# OctoSlime_Haptics_Module.net
KiCad netlist of a schematic drawn in EasyEDA Pro
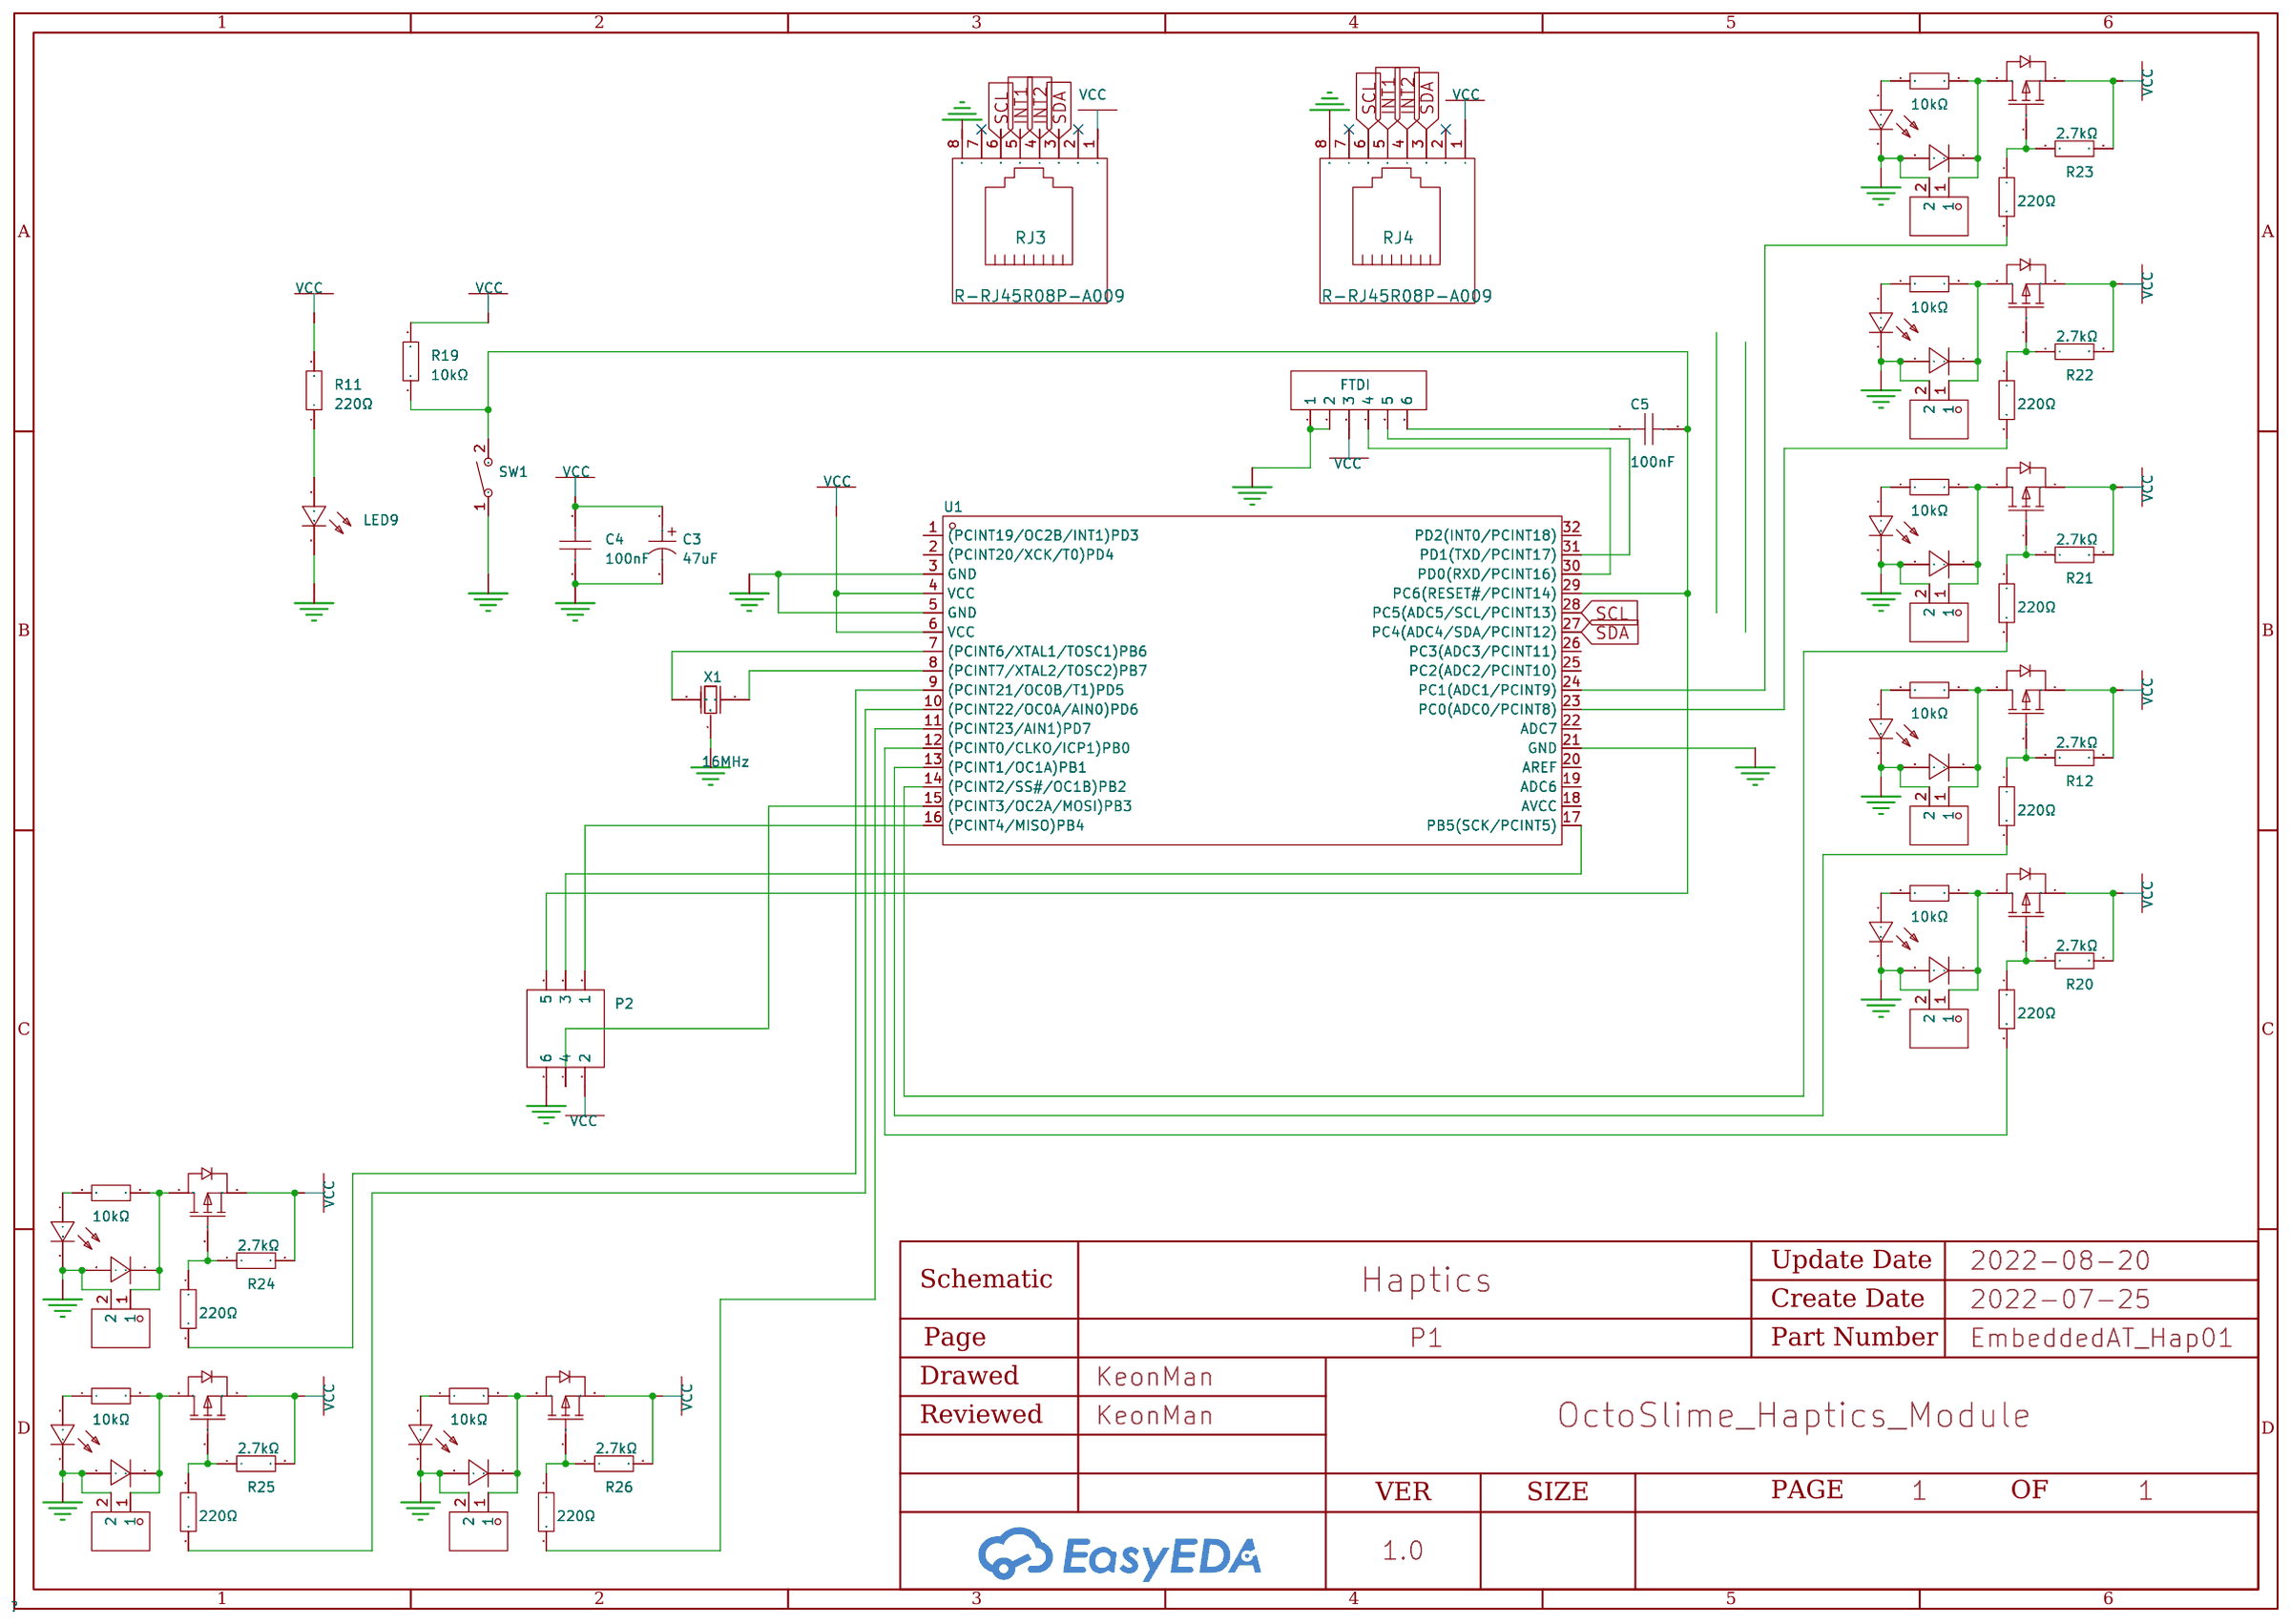
[diagram p0: schematic sheet]

(export (version "E")
  (design (tool "Eeschema 10.0.6"))
  (components
    (comp (ref "C3")
      (value "47uF")
      (footprint "easyedapro:CAP-SMD_L7.3-W4.3-FD")
      (description "容值:47uF;精度:±10%;额定电压:25V;等效串联电阻:900mΩ@100kHz;工作温度:-55~+125;")
      (fields (field (name "Manufacturer Part") "CA45-D-25V-47F-K") (field (name "Manufacturer") "TORCH(火炬)"))
      (libsource (lib "easyedapro") (part "CA45-D-25V-47μF-K"))
    )
    (comp (ref "C4")
      (value "100nF")
      (footprint "easyedapro:C0603")
      (description "容值:100nF;精度:±10%;额定电压:50V;温度系数:X7R;")
      (fields
        (field (name "Manufacturer Part") "CL10B104KB8NNNC")
        (field (name "Manufacturer") "SAMSUNG(三星)")
      )
      (libsource (lib "easyedapro") (part "CL10B104KB8NNNC"))
    )
    (comp (ref "C5")
      (value "100nF")
      (footprint "easyedapro:C0603")
      (description "容值:100nF;精度:±10%;额定电压:50V;温度系数:X7R;")
      (fields
        (field (name "Manufacturer Part") "CL10B104KB8NNNC")
        (field (name "Manufacturer") "SAMSUNG(三星)")
      )
      (libsource (lib "easyedapro") (part "CL10B104KB8NNNC"))
    )
    (comp (ref "CN1")
      (value "~")
      (footprint "easyedapro:CONN-TH_2P-P2.50_HX25003-2WAP")
      (description "俗称： XH2.54 配套：HX25002-2Y")
      (fields (field (name "Manufacturer Part") "HX25003-2WAP") (field (name "Manufacturer") "HX(红星)"))
      (libsource (lib "easyedapro") (part "HX25003-2WAP"))
    )
    (comp (ref "CN2")
      (value "~")
      (footprint "easyedapro:CONN-TH_2P-P2.50_HX25003-2WAP")
      (description "俗称： XH2.54 配套：HX25002-2Y")
      (fields (field (name "Manufacturer Part") "HX25003-2WAP") (field (name "Manufacturer") "HX(红星)"))
      (libsource (lib "easyedapro") (part "HX25003-2WAP"))
    )
    (comp (ref "CN3")
      (value "~")
      (footprint "easyedapro:CONN-TH_2P-P2.50_HX25003-2WAP")
      (description "俗称： XH2.54 配套：HX25002-2Y")
      (fields (field (name "Manufacturer Part") "HX25003-2WAP") (field (name "Manufacturer") "HX(红星)"))
      (libsource (lib "easyedapro") (part "HX25003-2WAP"))
    )
    (comp (ref "CN4")
      (value "~")
      (footprint "easyedapro:CONN-TH_2P-P2.50_HX25003-2WAP")
      (description "俗称： XH2.54 配套：HX25002-2Y")
      (fields (field (name "Manufacturer Part") "HX25003-2WAP") (field (name "Manufacturer") "HX(红星)"))
      (libsource (lib "easyedapro") (part "HX25003-2WAP"))
    )
    (comp (ref "CN5")
      (value "~")
      (footprint "easyedapro:CONN-TH_2P-P2.50_HX25003-2WAP")
      (description "俗称： XH2.54 配套：HX25002-2Y")
      (fields (field (name "Manufacturer Part") "HX25003-2WAP") (field (name "Manufacturer") "HX(红星)"))
      (libsource (lib "easyedapro") (part "HX25003-2WAP"))
    )
    (comp (ref "CN6")
      (value "~")
      (footprint "easyedapro:CONN-TH_2P-P2.50_HX25003-2WAP")
      (description "俗称： XH2.54 配套：HX25002-2Y")
      (fields (field (name "Manufacturer Part") "HX25003-2WAP") (field (name "Manufacturer") "HX(红星)"))
      (libsource (lib "easyedapro") (part "HX25003-2WAP"))
    )
    (comp (ref "CN7")
      (value "~")
      (footprint "easyedapro:CONN-TH_2P-P2.50_HX25003-2WAP")
      (description "俗称： XH2.54 配套：HX25002-2Y")
      (fields (field (name "Manufacturer Part") "HX25003-2WAP") (field (name "Manufacturer") "HX(红星)"))
      (libsource (lib "easyedapro") (part "HX25003-2WAP"))
    )
    (comp (ref "CN8")
      (value "~")
      (footprint "easyedapro:CONN-TH_2P-P2.50_HX25003-2WAP")
      (description "俗称： XH2.54 配套：HX25002-2Y")
      (fields (field (name "Manufacturer Part") "HX25003-2WAP") (field (name "Manufacturer") "HX(红星)"))
      (libsource (lib "easyedapro") (part "HX25003-2WAP"))
    )
    (comp (ref "D1")
      (value "~")
      (footprint "easyedapro:DO-214AC_L4.3-W2.7-LS5.3-RD")
      (description "二极管配置:-;直流反向耐压(Vr):1kV;平均整流电流(Io):1A;正向压降(Vf):1.1V@1A;反向电流(Ir):5A@1kV;")
      (fields (field (name "Manufacturer Part") "M7") (field (name "Manufacturer") "MDD"))
      (libsource (lib "easyedapro") (part "M7_C95872"))
    )
    (comp (ref "D2")
      (value "~")
      (footprint "easyedapro:DO-214AC_L4.3-W2.7-LS5.3-RD")
      (description "二极管配置:-;直流反向耐压(Vr):1kV;平均整流电流(Io):1A;正向压降(Vf):1.1V@1A;反向电流(Ir):5A@1kV;")
      (fields (field (name "Manufacturer Part") "M7") (field (name "Manufacturer") "MDD"))
      (libsource (lib "easyedapro") (part "M7_C95872"))
    )
    (comp (ref "D3")
      (value "~")
      (footprint "easyedapro:DO-214AC_L4.3-W2.7-LS5.3-RD")
      (description "二极管配置:-;直流反向耐压(Vr):1kV;平均整流电流(Io):1A;正向压降(Vf):1.1V@1A;反向电流(Ir):5A@1kV;")
      (fields (field (name "Manufacturer Part") "M7") (field (name "Manufacturer") "MDD"))
      (libsource (lib "easyedapro") (part "M7_C95872"))
    )
    (comp (ref "D4")
      (value "~")
      (footprint "easyedapro:DO-214AC_L4.3-W2.7-LS5.3-RD")
      (description "二极管配置:-;直流反向耐压(Vr):1kV;平均整流电流(Io):1A;正向压降(Vf):1.1V@1A;反向电流(Ir):5A@1kV;")
      (fields (field (name "Manufacturer Part") "M7") (field (name "Manufacturer") "MDD"))
      (libsource (lib "easyedapro") (part "M7_C95872"))
    )
    (comp (ref "D5")
      (value "~")
      (footprint "easyedapro:DO-214AC_L4.3-W2.7-LS5.3-RD")
      (description "二极管配置:-;直流反向耐压(Vr):1kV;平均整流电流(Io):1A;正向压降(Vf):1.1V@1A;反向电流(Ir):5A@1kV;")
      (fields (field (name "Manufacturer Part") "M7") (field (name "Manufacturer") "MDD"))
      (libsource (lib "easyedapro") (part "M7_C95872"))
    )
    (comp (ref "D6")
      (value "~")
      (footprint "easyedapro:DO-214AC_L4.3-W2.7-LS5.3-RD")
      (description "二极管配置:-;直流反向耐压(Vr):1kV;平均整流电流(Io):1A;正向压降(Vf):1.1V@1A;反向电流(Ir):5A@1kV;")
      (fields (field (name "Manufacturer Part") "M7") (field (name "Manufacturer") "MDD"))
      (libsource (lib "easyedapro") (part "M7_C95872"))
    )
    (comp (ref "D7")
      (value "~")
      (footprint "easyedapro:DO-214AC_L4.3-W2.7-LS5.3-RD")
      (description "二极管配置:-;直流反向耐压(Vr):1kV;平均整流电流(Io):1A;正向压降(Vf):1.1V@1A;反向电流(Ir):5A@1kV;")
      (fields (field (name "Manufacturer Part") "M7") (field (name "Manufacturer") "MDD"))
      (libsource (lib "easyedapro") (part "M7_C95872"))
    )
    (comp (ref "D8")
      (value "~")
      (footprint "easyedapro:DO-214AC_L4.3-W2.7-LS5.3-RD")
      (description "二极管配置:-;直流反向耐压(Vr):1kV;平均整流电流(Io):1A;正向压降(Vf):1.1V@1A;反向电流(Ir):5A@1kV;")
      (fields (field (name "Manufacturer Part") "M7") (field (name "Manufacturer") "MDD"))
      (libsource (lib "easyedapro") (part "M7_C95872"))
    )
    (comp (ref "FTDI")
      (value "~")
      (footprint "easyedapro:HDR-TH_6P-P2.54-V-M-1")
      (fields (field (name "Manufacturer Part") "2.54-1x6P直针") (field (name "Manufacturer") "BOOMELE(博穆精密)"))
      (libsource (lib "easyedapro") (part "Header-Male-2.54_1x6"))
    )
    (comp (ref "LED1")
      (value "~")
      (footprint "easyedapro:LED0603-R-RD")
      (description "发光颜色:红灯;")
      (fields
        (field (name "Manufacturer Part") "19-213/R6C-AP1Q2B/3T")
        (field (name "Manufacturer") "EVERLIGHT(台湾亿光)")
      )
      (libsource (lib "easyedapro") (part "19-213/R6C-AP1Q2B/3T_C128051"))
    )
    (comp (ref "LED2")
      (value "~")
      (footprint "easyedapro:LED0603-R-RD")
      (description "发光颜色:红灯;")
      (fields
        (field (name "Manufacturer Part") "19-213/R6C-AP1Q2B/3T")
        (field (name "Manufacturer") "EVERLIGHT(台湾亿光)")
      )
      (libsource (lib "easyedapro") (part "19-213/R6C-AP1Q2B/3T_C128051"))
    )
    (comp (ref "LED3")
      (value "~")
      (footprint "easyedapro:LED0603-R-RD")
      (description "发光颜色:红灯;")
      (fields
        (field (name "Manufacturer Part") "19-213/R6C-AP1Q2B/3T")
        (field (name "Manufacturer") "EVERLIGHT(台湾亿光)")
      )
      (libsource (lib "easyedapro") (part "19-213/R6C-AP1Q2B/3T_C128051"))
    )
    (comp (ref "LED4")
      (value "~")
      (footprint "easyedapro:LED0603-R-RD")
      (description "发光颜色:红灯;")
      (fields
        (field (name "Manufacturer Part") "19-213/R6C-AP1Q2B/3T")
        (field (name "Manufacturer") "EVERLIGHT(台湾亿光)")
      )
      (libsource (lib "easyedapro") (part "19-213/R6C-AP1Q2B/3T_C128051"))
    )
    (comp (ref "LED5")
      (value "~")
      (footprint "easyedapro:LED0603-R-RD")
      (description "发光颜色:红灯;")
      (fields
        (field (name "Manufacturer Part") "19-213/R6C-AP1Q2B/3T")
        (field (name "Manufacturer") "EVERLIGHT(台湾亿光)")
      )
      (libsource (lib "easyedapro") (part "19-213/R6C-AP1Q2B/3T_C128051"))
    )
    (comp (ref "LED6")
      (value "~")
      (footprint "easyedapro:LED0603-R-RD")
      (description "发光颜色:红灯;")
      (fields
        (field (name "Manufacturer Part") "19-213/R6C-AP1Q2B/3T")
        (field (name "Manufacturer") "EVERLIGHT(台湾亿光)")
      )
      (libsource (lib "easyedapro") (part "19-213/R6C-AP1Q2B/3T_C128051"))
    )
    (comp (ref "LED7")
      (value "~")
      (footprint "easyedapro:LED0603-R-RD")
      (description "发光颜色:红灯;")
      (fields
        (field (name "Manufacturer Part") "19-213/R6C-AP1Q2B/3T")
        (field (name "Manufacturer") "EVERLIGHT(台湾亿光)")
      )
      (libsource (lib "easyedapro") (part "19-213/R6C-AP1Q2B/3T_C128051"))
    )
    (comp (ref "LED8")
      (value "~")
      (footprint "easyedapro:LED0603-R-RD")
      (description "发光颜色:红灯;")
      (fields
        (field (name "Manufacturer Part") "19-213/R6C-AP1Q2B/3T")
        (field (name "Manufacturer") "EVERLIGHT(台湾亿光)")
      )
      (libsource (lib "easyedapro") (part "19-213/R6C-AP1Q2B/3T_C128051"))
    )
    (comp (ref "LED9")
      (value "~")
      (footprint "easyedapro:LED0603-R-RD")
      (description "发光颜色:红灯;")
      (fields
        (field (name "Manufacturer Part") "19-213/R6C-AP1Q2B/3T")
        (field (name "Manufacturer") "EVERLIGHT(台湾亿光)")
      )
      (libsource (lib "easyedapro") (part "19-213/R6C-AP1Q2B/3T_C128051"))
    )
    (comp (ref "P2")
      (value "~")
      (footprint "easyedapro:IDC-TH_6P-P2.54_C11214")
      (description "连接器类型:简牛座;间距:2.54mm;排数:2;行距:2.54mm;封装形式:直插;触头材质:黄铜;触头镀层:金;")
      (fields (field (name "Manufacturer Part") "2.54-2*3P简牛") (field (name "Manufacturer") "BOOMELE(博穆精密)"))
      (libsource (lib "easyedapro") (part "HDR-IDC-2.54-2X3P"))
    )
    (comp (ref "Q1")
      (value "~")
      (footprint "easyedapro:SC-70-3_L2.2-W1.2-P1.30-LS2.1-BL")
      (fields (field (name "Manufacturer Part") "CJ2101") (field (name "Manufacturer") "CJ（江苏长电/长晶）"))
      (libsource (lib "easyedapro") (part "CJ2101"))
    )
    (comp (ref "Q2")
      (value "~")
      (footprint "easyedapro:SC-70-3_L2.2-W1.2-P1.30-LS2.1-BL")
      (fields (field (name "Manufacturer Part") "CJ2101") (field (name "Manufacturer") "CJ（江苏长电/长晶）"))
      (libsource (lib "easyedapro") (part "CJ2101"))
    )
    (comp (ref "Q3")
      (value "~")
      (footprint "easyedapro:SC-70-3_L2.2-W1.2-P1.30-LS2.1-BL")
      (fields (field (name "Manufacturer Part") "CJ2101") (field (name "Manufacturer") "CJ（江苏长电/长晶）"))
      (libsource (lib "easyedapro") (part "CJ2101"))
    )
    (comp (ref "Q4")
      (value "~")
      (footprint "easyedapro:SC-70-3_L2.2-W1.2-P1.30-LS2.1-BL")
      (fields (field (name "Manufacturer Part") "CJ2101") (field (name "Manufacturer") "CJ（江苏长电/长晶）"))
      (libsource (lib "easyedapro") (part "CJ2101"))
    )
    (comp (ref "Q5")
      (value "~")
      (footprint "easyedapro:SC-70-3_L2.2-W1.2-P1.30-LS2.1-BL")
      (fields (field (name "Manufacturer Part") "CJ2101") (field (name "Manufacturer") "CJ（江苏长电/长晶）"))
      (libsource (lib "easyedapro") (part "CJ2101"))
    )
    (comp (ref "Q6")
      (value "~")
      (footprint "easyedapro:SC-70-3_L2.2-W1.2-P1.30-LS2.1-BL")
      (fields (field (name "Manufacturer Part") "CJ2101") (field (name "Manufacturer") "CJ（江苏长电/长晶）"))
      (libsource (lib "easyedapro") (part "CJ2101"))
    )
    (comp (ref "Q7")
      (value "~")
      (footprint "easyedapro:SC-70-3_L2.2-W1.2-P1.30-LS2.1-BL")
      (fields (field (name "Manufacturer Part") "CJ2101") (field (name "Manufacturer") "CJ（江苏长电/长晶）"))
      (libsource (lib "easyedapro") (part "CJ2101"))
    )
    (comp (ref "Q8")
      (value "~")
      (footprint "easyedapro:SC-70-3_L2.2-W1.2-P1.30-LS2.1-BL")
      (fields (field (name "Manufacturer Part") "CJ2101") (field (name "Manufacturer") "CJ（江苏长电/长晶）"))
      (libsource (lib "easyedapro") (part "CJ2101"))
    )
    (comp (ref "R1")
      (value "220Ω")
      (footprint "easyedapro:R1206")
      (description "电阻类型:厚膜电阻;阻值:220Ω;精度:±1%;功率:250mW;温度系数:±100ppm/;最大工作电压:200V;工作温度范围:-55~+155;")
      (fields (field (name "Manufacturer Part") "RC1206FR-07220RL") (field (name "Manufacturer") "YAGEO(国巨)"))
      (libsource (lib "easyedapro") (part "RC1206FR-07220RL"))
    )
    (comp (ref "R2")
      (value "220Ω")
      (footprint "easyedapro:R1206")
      (description "电阻类型:厚膜电阻;阻值:220Ω;精度:±1%;功率:250mW;温度系数:±100ppm/;最大工作电压:200V;工作温度范围:-55~+155;")
      (fields (field (name "Manufacturer Part") "RC1206FR-07220RL") (field (name "Manufacturer") "YAGEO(国巨)"))
      (libsource (lib "easyedapro") (part "RC1206FR-07220RL"))
    )
    (comp (ref "R3")
      (value "10kΩ")
      (footprint "easyedapro:R0603")
      (description "电阻类型:薄膜电阻;阻值:10kΩ;精度:±0.1%;功率:100mW;温度系数:±50ppm/;最大工作电压:50V;工作温度范围:-55~+155;")
      (fields (field (name "Manufacturer Part") "AR03BTDX1002") (field (name "Manufacturer") "光颉(Viking)"))
      (libsource (lib "easyedapro") (part "AR03BTDX1002"))
    )
    (comp (ref "R4")
      (value "220Ω")
      (footprint "easyedapro:R1206")
      (description "电阻类型:厚膜电阻;阻值:220Ω;精度:±1%;功率:250mW;温度系数:±100ppm/;最大工作电压:200V;工作温度范围:-55~+155;")
      (fields (field (name "Manufacturer Part") "RC1206FR-07220RL") (field (name "Manufacturer") "YAGEO(国巨)"))
      (libsource (lib "easyedapro") (part "RC1206FR-07220RL"))
    )
    (comp (ref "R5")
      (value "10kΩ")
      (footprint "easyedapro:R0603")
      (description "电阻类型:薄膜电阻;阻值:10kΩ;精度:±0.1%;功率:100mW;温度系数:±50ppm/;最大工作电压:50V;工作温度范围:-55~+155;")
      (fields (field (name "Manufacturer Part") "AR03BTDX1002") (field (name "Manufacturer") "光颉(Viking)"))
      (libsource (lib "easyedapro") (part "AR03BTDX1002"))
    )
    (comp (ref "R6")
      (value "220Ω")
      (footprint "easyedapro:R1206")
      (description "电阻类型:厚膜电阻;阻值:220Ω;精度:±1%;功率:250mW;温度系数:±100ppm/;最大工作电压:200V;工作温度范围:-55~+155;")
      (fields (field (name "Manufacturer Part") "RC1206FR-07220RL") (field (name "Manufacturer") "YAGEO(国巨)"))
      (libsource (lib "easyedapro") (part "RC1206FR-07220RL"))
    )
    (comp (ref "R7")
      (value "10kΩ")
      (footprint "easyedapro:R0603")
      (description "电阻类型:薄膜电阻;阻值:10kΩ;精度:±0.1%;功率:100mW;温度系数:±50ppm/;最大工作电压:50V;工作温度范围:-55~+155;")
      (fields (field (name "Manufacturer Part") "AR03BTDX1002") (field (name "Manufacturer") "光颉(Viking)"))
      (libsource (lib "easyedapro") (part "AR03BTDX1002"))
    )
    (comp (ref "R8")
      (value "220Ω")
      (footprint "easyedapro:R1206")
      (description "电阻类型:厚膜电阻;阻值:220Ω;精度:±1%;功率:250mW;温度系数:±100ppm/;最大工作电压:200V;工作温度范围:-55~+155;")
      (fields (field (name "Manufacturer Part") "RC1206FR-07220RL") (field (name "Manufacturer") "YAGEO(国巨)"))
      (libsource (lib "easyedapro") (part "RC1206FR-07220RL"))
    )
    (comp (ref "R9")
      (value "10kΩ")
      (footprint "easyedapro:R0603")
      (description "电阻类型:薄膜电阻;阻值:10kΩ;精度:±0.1%;功率:100mW;温度系数:±50ppm/;最大工作电压:50V;工作温度范围:-55~+155;")
      (fields (field (name "Manufacturer Part") "AR03BTDX1002") (field (name "Manufacturer") "光颉(Viking)"))
      (libsource (lib "easyedapro") (part "AR03BTDX1002"))
    )
    (comp (ref "R10")
      (value "220Ω")
      (footprint "easyedapro:R1206")
      (description "电阻类型:厚膜电阻;阻值:220Ω;精度:±1%;功率:250mW;温度系数:±100ppm/;最大工作电压:200V;工作温度范围:-55~+155;")
      (fields (field (name "Manufacturer Part") "RC1206FR-07220RL") (field (name "Manufacturer") "YAGEO(国巨)"))
      (libsource (lib "easyedapro") (part "RC1206FR-07220RL"))
    )
    (comp (ref "R11")
      (value "220Ω")
      (footprint "easyedapro:R1206")
      (description "电阻类型:厚膜电阻;阻值:220Ω;精度:±1%;功率:250mW;温度系数:±100ppm/;最大工作电压:200V;工作温度范围:-55~+155;")
      (fields (field (name "Manufacturer Part") "RC1206FR-07220RL") (field (name "Manufacturer") "YAGEO(国巨)"))
      (libsource (lib "easyedapro") (part "RC1206FR-07220RL"))
    )
    (comp (ref "R12")
      (value "2.7kΩ")
      (footprint "easyedapro:R0603")
      (description "电阻类型:厚膜电阻;阻值:2.7kΩ;精度:±1%;功率:100mW;温度系数:±100ppm/;最大工作电压:75V;工作温度范围:-55~+155;")
      (fields
        (field (name "Manufacturer Part") "0603WAF2701T5E")
        (field (name "Manufacturer") "UNI-ROYAL(厚声)")
      )
      (libsource (lib "easyedapro") (part "0603WAF2701T5E"))
    )
    (comp (ref "R13")
      (value "10kΩ")
      (footprint "easyedapro:R0603")
      (description "电阻类型:薄膜电阻;阻值:10kΩ;精度:±0.1%;功率:100mW;温度系数:±50ppm/;最大工作电压:50V;工作温度范围:-55~+155;")
      (fields (field (name "Manufacturer Part") "AR03BTDX1002") (field (name "Manufacturer") "光颉(Viking)"))
      (libsource (lib "easyedapro") (part "AR03BTDX1002"))
    )
    (comp (ref "R14")
      (value "10kΩ")
      (footprint "easyedapro:R0603")
      (description "电阻类型:薄膜电阻;阻值:10kΩ;精度:±0.1%;功率:100mW;温度系数:±50ppm/;最大工作电压:50V;工作温度范围:-55~+155;")
      (fields (field (name "Manufacturer Part") "AR03BTDX1002") (field (name "Manufacturer") "光颉(Viking)"))
      (libsource (lib "easyedapro") (part "AR03BTDX1002"))
    )
    (comp (ref "R15")
      (value "220Ω")
      (footprint "easyedapro:R1206")
      (description "电阻类型:厚膜电阻;阻值:220Ω;精度:±1%;功率:250mW;温度系数:±100ppm/;最大工作电压:200V;工作温度范围:-55~+155;")
      (fields (field (name "Manufacturer Part") "RC1206FR-07220RL") (field (name "Manufacturer") "YAGEO(国巨)"))
      (libsource (lib "easyedapro") (part "RC1206FR-07220RL"))
    )
    (comp (ref "R16")
      (value "10kΩ")
      (footprint "easyedapro:R0603")
      (description "电阻类型:薄膜电阻;阻值:10kΩ;精度:±0.1%;功率:100mW;温度系数:±50ppm/;最大工作电压:50V;工作温度范围:-55~+155;")
      (fields (field (name "Manufacturer Part") "AR03BTDX1002") (field (name "Manufacturer") "光颉(Viking)"))
      (libsource (lib "easyedapro") (part "AR03BTDX1002"))
    )
    (comp (ref "R17")
      (value "220Ω")
      (footprint "easyedapro:R1206")
      (description "电阻类型:厚膜电阻;阻值:220Ω;精度:±1%;功率:250mW;温度系数:±100ppm/;最大工作电压:200V;工作温度范围:-55~+155;")
      (fields (field (name "Manufacturer Part") "RC1206FR-07220RL") (field (name "Manufacturer") "YAGEO(国巨)"))
      (libsource (lib "easyedapro") (part "RC1206FR-07220RL"))
    )
    (comp (ref "R18")
      (value "10kΩ")
      (footprint "easyedapro:R0603")
      (description "电阻类型:薄膜电阻;阻值:10kΩ;精度:±0.1%;功率:100mW;温度系数:±50ppm/;最大工作电压:50V;工作温度范围:-55~+155;")
      (fields (field (name "Manufacturer Part") "AR03BTDX1002") (field (name "Manufacturer") "光颉(Viking)"))
      (libsource (lib "easyedapro") (part "AR03BTDX1002"))
    )
    (comp (ref "R19")
      (value "10kΩ")
      (footprint "easyedapro:R0603")
      (description "电阻类型:薄膜电阻;阻值:10kΩ;精度:±0.1%;功率:100mW;温度系数:±50ppm/;最大工作电压:50V;工作温度范围:-55~+155;")
      (fields (field (name "Manufacturer Part") "AR03BTDX1002") (field (name "Manufacturer") "光颉(Viking)"))
      (libsource (lib "easyedapro") (part "AR03BTDX1002"))
    )
    (comp (ref "R20")
      (value "2.7kΩ")
      (footprint "easyedapro:R0603")
      (description "电阻类型:厚膜电阻;阻值:2.7kΩ;精度:±1%;功率:100mW;温度系数:±100ppm/;最大工作电压:75V;工作温度范围:-55~+155;")
      (fields
        (field (name "Manufacturer Part") "0603WAF2701T5E")
        (field (name "Manufacturer") "UNI-ROYAL(厚声)")
      )
      (libsource (lib "easyedapro") (part "0603WAF2701T5E"))
    )
    (comp (ref "R21")
      (value "2.7kΩ")
      (footprint "easyedapro:R0603")
      (description "电阻类型:厚膜电阻;阻值:2.7kΩ;精度:±1%;功率:100mW;温度系数:±100ppm/;最大工作电压:75V;工作温度范围:-55~+155;")
      (fields
        (field (name "Manufacturer Part") "0603WAF2701T5E")
        (field (name "Manufacturer") "UNI-ROYAL(厚声)")
      )
      (libsource (lib "easyedapro") (part "0603WAF2701T5E"))
    )
    (comp (ref "R22")
      (value "2.7kΩ")
      (footprint "easyedapro:R0603")
      (description "电阻类型:厚膜电阻;阻值:2.7kΩ;精度:±1%;功率:100mW;温度系数:±100ppm/;最大工作电压:75V;工作温度范围:-55~+155;")
      (fields
        (field (name "Manufacturer Part") "0603WAF2701T5E")
        (field (name "Manufacturer") "UNI-ROYAL(厚声)")
      )
      (libsource (lib "easyedapro") (part "0603WAF2701T5E"))
    )
    (comp (ref "R23")
      (value "2.7kΩ")
      (footprint "easyedapro:R0603")
      (description "电阻类型:厚膜电阻;阻值:2.7kΩ;精度:±1%;功率:100mW;温度系数:±100ppm/;最大工作电压:75V;工作温度范围:-55~+155;")
      (fields
        (field (name "Manufacturer Part") "0603WAF2701T5E")
        (field (name "Manufacturer") "UNI-ROYAL(厚声)")
      )
      (libsource (lib "easyedapro") (part "0603WAF2701T5E"))
    )
    (comp (ref "R24")
      (value "2.7kΩ")
      (footprint "easyedapro:R0603")
      (description "电阻类型:厚膜电阻;阻值:2.7kΩ;精度:±1%;功率:100mW;温度系数:±100ppm/;最大工作电压:75V;工作温度范围:-55~+155;")
      (fields
        (field (name "Manufacturer Part") "0603WAF2701T5E")
        (field (name "Manufacturer") "UNI-ROYAL(厚声)")
      )
      (libsource (lib "easyedapro") (part "0603WAF2701T5E"))
    )
    (comp (ref "R25")
      (value "2.7kΩ")
      (footprint "easyedapro:R0603")
      (description "电阻类型:厚膜电阻;阻值:2.7kΩ;精度:±1%;功率:100mW;温度系数:±100ppm/;最大工作电压:75V;工作温度范围:-55~+155;")
      (fields
        (field (name "Manufacturer Part") "0603WAF2701T5E")
        (field (name "Manufacturer") "UNI-ROYAL(厚声)")
      )
      (libsource (lib "easyedapro") (part "0603WAF2701T5E"))
    )
    (comp (ref "R26")
      (value "2.7kΩ")
      (footprint "easyedapro:R0603")
      (description "电阻类型:厚膜电阻;阻值:2.7kΩ;精度:±1%;功率:100mW;温度系数:±100ppm/;最大工作电压:75V;工作温度范围:-55~+155;")
      (fields
        (field (name "Manufacturer Part") "0603WAF2701T5E")
        (field (name "Manufacturer") "UNI-ROYAL(厚声)")
      )
      (libsource (lib "easyedapro") (part "0603WAF2701T5E"))
    )
    (comp (ref "RJ3")
      (value "R-RJ45R08P-A009")
      (footprint "easyedapro:RJ45-TH_R-RJ45R08P-A009")
      (fields (field (name "Manufacturer") "Ckmtw(灿科盟)"))
      (libsource (lib "easyedapro") (part "R-RJ45R08P-A009"))
    )
    (comp (ref "RJ4")
      (value "R-RJ45R08P-A009")
      (footprint "easyedapro:RJ45-TH_R-RJ45R08P-A009")
      (fields (field (name "Manufacturer") "Ckmtw(灿科盟)"))
      (libsource (lib "easyedapro") (part "R-RJ45R08P-A009"))
    )
    (comp (ref "SW1")
      (value "~")
      (footprint "easyedapro:SW-SMD_L4.0-W2.9-LS5.0")
      (fields (field (name "Manufacturer Part") "TS342A2P-WZ") (field (name "Manufacturer") "SHOU HAN(首韩)"))
      (libsource (lib "easyedapro") (part "TS342A2P-WZ"))
    )
    (comp (ref "U1")
      (value "~")
      (footprint "easyedapro:TQFP-32_L7.0-W7.0-P0.80-LS9.0-BL")
      (description "CPU内核:AVR;主频（MAX):20MHz;工作电压:1.8V ~ 5.5V;")
      (fields
        (field (name "Manufacturer Part") "ATMEGA328P-AU")
        (field (name "Manufacturer") "MICROCHIP(美国微芯)")
      )
      (libsource (lib "easyedapro") (part "ATMEGA328P-AU"))
    )
    (comp (ref "X1")
      (value "16MHz")
      (footprint "easyedapro:OSC-SMD_3P-L3.2-W1.3-P1.2-L")
      (description "频率:16MHz;频率容差:±0.5%;内藏负载电容:15pF;谐振阻抗:40Ω;")
      (fields
        (field (name "Manufacturer Part") "CSTNE16M0V530000R0")
        (field (name "Manufacturer") "muRata(村田)")
      )
      (libsource (lib "easyedapro") (part "CSTNE16M0V530000R0"))
    )
  )
  (nets
    (net (code "1") (name "GND") (class "Default")
      (node (ref "C3") (pin "2") (pinfunction "2_2") (pintype "input"))
      (node (ref "C4") (pin "1") (pinfunction "1_1") (pintype "input"))
      (node (ref "CN1") (pin "2") (pinfunction "2_2") (pintype "input"))
      (node (ref "CN2") (pin "2") (pinfunction "2_2") (pintype "input"))
      (node (ref "CN3") (pin "2") (pinfunction "2_2") (pintype "input"))
      (node (ref "CN4") (pin "2") (pinfunction "2_2") (pintype "input"))
      (node (ref "CN5") (pin "2") (pinfunction "2_2") (pintype "input"))
      (node (ref "CN6") (pin "2") (pinfunction "2_2") (pintype "input"))
      (node (ref "CN7") (pin "2") (pinfunction "2_2") (pintype "input"))
      (node (ref "CN8") (pin "2") (pinfunction "2_2") (pintype "input"))
      (node (ref "D1") (pin "2") (pinfunction "A_2") (pintype "input"))
      (node (ref "D2") (pin "2") (pinfunction "A_2") (pintype "input"))
      (node (ref "D3") (pin "2") (pinfunction "A_2") (pintype "input"))
      (node (ref "D4") (pin "2") (pinfunction "A_2") (pintype "input"))
      (node (ref "D5") (pin "2") (pinfunction "A_2") (pintype "input"))
      (node (ref "D6") (pin "2") (pinfunction "A_2") (pintype "input"))
      (node (ref "D7") (pin "2") (pinfunction "A_2") (pintype "input"))
      (node (ref "D8") (pin "2") (pinfunction "A_2") (pintype "input"))
      (node (ref "FTDI") (pin "1") (pinfunction "1_1") (pintype "input"))
      (node (ref "FTDI") (pin "2") (pinfunction "2_2") (pintype "input"))
      (node (ref "LED1") (pin "2") (pinfunction "C_2") (pintype "input"))
      (node (ref "LED2") (pin "2") (pinfunction "C_2") (pintype "input"))
      (node (ref "LED3") (pin "2") (pinfunction "C_2") (pintype "input"))
      (node (ref "LED4") (pin "2") (pinfunction "C_2") (pintype "input"))
      (node (ref "LED5") (pin "2") (pinfunction "C_2") (pintype "input"))
      (node (ref "LED6") (pin "2") (pinfunction "C_2") (pintype "input"))
      (node (ref "LED7") (pin "2") (pinfunction "C_2") (pintype "input"))
      (node (ref "LED8") (pin "2") (pinfunction "C_2") (pintype "input"))
      (node (ref "LED9") (pin "2") (pinfunction "C_2") (pintype "input"))
      (node (ref "P2") (pin "6") (pinfunction "6_6") (pintype "input"))
      (node (ref "RJ3") (pin "8") (pinfunction "8_8") (pintype "input"))
      (node (ref "RJ4") (pin "8") (pinfunction "8_8") (pintype "input"))
      (node (ref "SW1") (pin "1") (pinfunction "1_1") (pintype "input"))
      (node (ref "U1") (pin "21") (pinfunction "GND_21") (pintype "input"))
      (node (ref "U1") (pin "3") (pinfunction "GND_3") (pintype "input"))
      (node (ref "U1") (pin "5") (pinfunction "GND_5") (pintype "input"))
      (node (ref "X1") (pin "2") (pinfunction "GND_2") (pintype "input"))
    )
    (net (code "2") (name "INT1") (class "Default")
      (node (ref "RJ3") (pin "5") (pinfunction "5_5") (pintype "input"))
      (node (ref "RJ4") (pin "5") (pinfunction "5_5") (pintype "input"))
    )
    (net (code "3") (name "INT2") (class "Default")
      (node (ref "RJ3") (pin "4") (pinfunction "4_4") (pintype "input"))
      (node (ref "RJ4") (pin "4") (pinfunction "4_4") (pintype "input"))
    )
    (net (code "4") (name "Net-(C5-Pad1)") (class "Default")
      (node (ref "C5") (pin "1") (pinfunction "1_1") (pintype "input"))
      (node (ref "FTDI") (pin "6") (pinfunction "6_6") (pintype "input"))
    )
    (net (code "5") (name "Net-(D1-K)") (class "Default")
      (node (ref "CN2") (pin "1") (pinfunction "1_1") (pintype "input"))
      (node (ref "D1") (pin "1") (pinfunction "K_1") (pintype "input"))
      (node (ref "Q2") (pin "3") (pinfunction "D_3") (pintype "input"))
      (node (ref "R3") (pin "2") (pinfunction "2_2") (pintype "input"))
    )
    (net (code "6") (name "Net-(D2-K)") (class "Default")
      (node (ref "CN3") (pin "1") (pinfunction "1_1") (pintype "input"))
      (node (ref "D2") (pin "1") (pinfunction "K_1") (pintype "input"))
      (node (ref "Q3") (pin "3") (pinfunction "D_3") (pintype "input"))
      (node (ref "R5") (pin "2") (pinfunction "2_2") (pintype "input"))
    )
    (net (code "7") (name "Net-(D3-K)") (class "Default")
      (node (ref "CN4") (pin "1") (pinfunction "1_1") (pintype "input"))
      (node (ref "D3") (pin "1") (pinfunction "K_1") (pintype "input"))
      (node (ref "Q4") (pin "3") (pinfunction "D_3") (pintype "input"))
      (node (ref "R7") (pin "2") (pinfunction "2_2") (pintype "input"))
    )
    (net (code "8") (name "Net-(D4-K)") (class "Default")
      (node (ref "CN5") (pin "1") (pinfunction "1_1") (pintype "input"))
      (node (ref "D4") (pin "1") (pinfunction "K_1") (pintype "input"))
      (node (ref "Q5") (pin "3") (pinfunction "D_3") (pintype "input"))
      (node (ref "R9") (pin "2") (pinfunction "2_2") (pintype "input"))
    )
    (net (code "9") (name "Net-(D5-K)") (class "Default")
      (node (ref "CN6") (pin "1") (pinfunction "1_1") (pintype "input"))
      (node (ref "D5") (pin "1") (pinfunction "K_1") (pintype "input"))
      (node (ref "Q6") (pin "3") (pinfunction "D_3") (pintype "input"))
      (node (ref "R14") (pin "2") (pinfunction "2_2") (pintype "input"))
    )
    (net (code "10") (name "Net-(D6-K)") (class "Default")
      (node (ref "CN7") (pin "1") (pinfunction "1_1") (pintype "input"))
      (node (ref "D6") (pin "1") (pinfunction "K_1") (pintype "input"))
      (node (ref "Q7") (pin "3") (pinfunction "D_3") (pintype "input"))
      (node (ref "R16") (pin "2") (pinfunction "2_2") (pintype "input"))
    )
    (net (code "11") (name "Net-(D7-K)") (class "Default")
      (node (ref "CN8") (pin "1") (pinfunction "1_1") (pintype "input"))
      (node (ref "D7") (pin "1") (pinfunction "K_1") (pintype "input"))
      (node (ref "Q8") (pin "3") (pinfunction "D_3") (pintype "input"))
      (node (ref "R18") (pin "2") (pinfunction "2_2") (pintype "input"))
    )
    (net (code "12") (name "Net-(D8-K)") (class "Default")
      (node (ref "CN1") (pin "1") (pinfunction "1_1") (pintype "input"))
      (node (ref "D8") (pin "1") (pinfunction "K_1") (pintype "input"))
      (node (ref "Q1") (pin "3") (pinfunction "D_3") (pintype "input"))
      (node (ref "R13") (pin "2") (pinfunction "2_2") (pintype "input"))
    )
    (net (code "13") (name "Net-(LED1-A)") (class "Default")
      (node (ref "LED1") (pin "1") (pinfunction "A_1") (pintype "input"))
      (node (ref "R13") (pin "1") (pinfunction "1_1") (pintype "input"))
    )
    (net (code "14") (name "Net-(LED2-A)") (class "Default")
      (node (ref "LED2") (pin "1") (pinfunction "A_1") (pintype "input"))
      (node (ref "R3") (pin "1") (pinfunction "1_1") (pintype "input"))
    )
    (net (code "15") (name "Net-(LED3-A)") (class "Default")
      (node (ref "LED3") (pin "1") (pinfunction "A_1") (pintype "input"))
      (node (ref "R5") (pin "1") (pinfunction "1_1") (pintype "input"))
    )
    (net (code "16") (name "Net-(LED4-A)") (class "Default")
      (node (ref "LED4") (pin "1") (pinfunction "A_1") (pintype "input"))
      (node (ref "R7") (pin "1") (pinfunction "1_1") (pintype "input"))
    )
    (net (code "17") (name "Net-(LED5-A)") (class "Default")
      (node (ref "LED5") (pin "1") (pinfunction "A_1") (pintype "input"))
      (node (ref "R9") (pin "1") (pinfunction "1_1") (pintype "input"))
    )
    (net (code "18") (name "Net-(LED6-A)") (class "Default")
      (node (ref "LED6") (pin "1") (pinfunction "A_1") (pintype "input"))
      (node (ref "R14") (pin "1") (pinfunction "1_1") (pintype "input"))
    )
    (net (code "19") (name "Net-(LED7-A)") (class "Default")
      (node (ref "LED7") (pin "1") (pinfunction "A_1") (pintype "input"))
      (node (ref "R16") (pin "1") (pinfunction "1_1") (pintype "input"))
    )
    (net (code "20") (name "Net-(LED8-A)") (class "Default")
      (node (ref "LED8") (pin "1") (pinfunction "A_1") (pintype "input"))
      (node (ref "R18") (pin "1") (pinfunction "1_1") (pintype "input"))
    )
    (net (code "21") (name "Net-(LED9-A)") (class "Default")
      (node (ref "LED9") (pin "1") (pinfunction "A_1") (pintype "input"))
      (node (ref "R11") (pin "1") (pinfunction "1_1") (pintype "input"))
    )
    (net (code "22") (name "Net-(Q1-G)") (class "Default")
      (node (ref "Q1") (pin "1") (pinfunction "G_1") (pintype "input"))
      (node (ref "R1") (pin "1") (pinfunction "1_1") (pintype "input"))
      (node (ref "R23") (pin "1") (pinfunction "1_1") (pintype "input"))
    )
    (net (code "23") (name "Net-(Q2-G)") (class "Default")
      (node (ref "Q2") (pin "1") (pinfunction "G_1") (pintype "input"))
      (node (ref "R2") (pin "1") (pinfunction "1_1") (pintype "input"))
      (node (ref "R22") (pin "1") (pinfunction "1_1") (pintype "input"))
    )
    (net (code "24") (name "Net-(Q3-G)") (class "Default")
      (node (ref "Q3") (pin "1") (pinfunction "G_1") (pintype "input"))
      (node (ref "R21") (pin "1") (pinfunction "1_1") (pintype "input"))
      (node (ref "R4") (pin "1") (pinfunction "1_1") (pintype "input"))
    )
    (net (code "25") (name "Net-(Q4-G)") (class "Default")
      (node (ref "Q4") (pin "1") (pinfunction "G_1") (pintype "input"))
      (node (ref "R12") (pin "1") (pinfunction "1_1") (pintype "input"))
      (node (ref "R6") (pin "1") (pinfunction "1_1") (pintype "input"))
    )
    (net (code "26") (name "Net-(Q5-G)") (class "Default")
      (node (ref "Q5") (pin "1") (pinfunction "G_1") (pintype "input"))
      (node (ref "R20") (pin "1") (pinfunction "1_1") (pintype "input"))
      (node (ref "R8") (pin "1") (pinfunction "1_1") (pintype "input"))
    )
    (net (code "27") (name "Net-(Q6-G)") (class "Default")
      (node (ref "Q6") (pin "1") (pinfunction "G_1") (pintype "input"))
      (node (ref "R10") (pin "1") (pinfunction "1_1") (pintype "input"))
      (node (ref "R26") (pin "1") (pinfunction "1_1") (pintype "input"))
    )
    (net (code "28") (name "Net-(Q7-G)") (class "Default")
      (node (ref "Q7") (pin "1") (pinfunction "G_1") (pintype "input"))
      (node (ref "R15") (pin "1") (pinfunction "1_1") (pintype "input"))
      (node (ref "R25") (pin "1") (pinfunction "1_1") (pintype "input"))
    )
    (net (code "29") (name "Net-(Q8-G)") (class "Default")
      (node (ref "Q8") (pin "1") (pinfunction "G_1") (pintype "input"))
      (node (ref "R17") (pin "1") (pinfunction "1_1") (pintype "input"))
      (node (ref "R24") (pin "1") (pinfunction "1_1") (pintype "input"))
    )
    (net (code "30") (name "Net-(U1-(PCINT0{slash}CLKO{slash}ICP1)PB0)") (class "Default")
      (node (ref "R8") (pin "2") (pinfunction "2_2") (pintype "input"))
      (node (ref "U1") (pin "12") (pinfunction "(PCINT0/CLKO/ICP1)PB0_12") (pintype "input"))
    )
    (net (code "31") (name "Net-(U1-(PCINT1{slash}OC1A)PB1)") (class "Default")
      (node (ref "R6") (pin "2") (pinfunction "2_2") (pintype "input"))
      (node (ref "U1") (pin "13") (pinfunction "(PCINT1/OC1A)PB1_13") (pintype "input"))
    )
    (net (code "32") (name "Net-(U1-(PCINT2{slash}SS#{slash}OC1B)PB2)") (class "Default")
      (node (ref "R4") (pin "2") (pinfunction "2_2") (pintype "input"))
      (node (ref "U1") (pin "14") (pinfunction "(PCINT2/SS#/OC1B)PB2_14") (pintype "input"))
    )
    (net (code "33") (name "Net-(U1-(PCINT3{slash}OC2A{slash}MOSI)PB3)") (class "Default")
      (node (ref "P2") (pin "4") (pinfunction "4_4") (pintype "input"))
      (node (ref "U1") (pin "15") (pinfunction "(PCINT3/OC2A/MOSI)PB3_15") (pintype "input"))
    )
    (net (code "34") (name "Net-(U1-(PCINT4{slash}MISO)PB4)") (class "Default")
      (node (ref "P2") (pin "1") (pinfunction "1_1") (pintype "input"))
      (node (ref "U1") (pin "16") (pinfunction "(PCINT4/MISO)PB4_16") (pintype "input"))
    )
    (net (code "35") (name "Net-(U1-(PCINT6{slash}XTAL1{slash}TOSC1)PB6)") (class "Default")
      (node (ref "U1") (pin "7") (pinfunction "(PCINT6/XTAL1/TOSC1)PB6_7") (pintype "input"))
      (node (ref "X1") (pin "3") (pinfunction "OSC2_3") (pintype "input"))
    )
    (net (code "36") (name "Net-(U1-(PCINT7{slash}XTAL2{slash}TOSC2)PB7)") (class "Default")
      (node (ref "U1") (pin "8") (pinfunction "(PCINT7/XTAL2/TOSC2)PB7_8") (pintype "input"))
      (node (ref "X1") (pin "1") (pinfunction "OSC1_1") (pintype "input"))
    )
    (net (code "37") (name "Net-(U1-(PCINT21{slash}OC0B{slash}T1)PD5)") (class "Default")
      (node (ref "R17") (pin "2") (pinfunction "2_2") (pintype "input"))
      (node (ref "U1") (pin "9") (pinfunction "(PCINT21/OC0B/T1)PD5_9") (pintype "input"))
    )
    (net (code "38") (name "Net-(U1-(PCINT22{slash}OC0A{slash}AIN0)PD6)") (class "Default")
      (node (ref "R15") (pin "2") (pinfunction "2_2") (pintype "input"))
      (node (ref "U1") (pin "10") (pinfunction "(PCINT22/OC0A/AIN0)PD6_10") (pintype "input"))
    )
    (net (code "39") (name "Net-(U1-(PCINT23{slash}AIN1)PD7)") (class "Default")
      (node (ref "R10") (pin "2") (pinfunction "2_2") (pintype "input"))
      (node (ref "U1") (pin "11") (pinfunction "(PCINT23/AIN1)PD7_11") (pintype "input"))
    )
    (net (code "40") (name "Net-(U1-PB5(SCK{slash}PCINT5))") (class "Default")
      (node (ref "P2") (pin "3") (pinfunction "3_3") (pintype "input"))
      (node (ref "U1") (pin "17") (pinfunction "PB5(SCK/PCINT5)_17") (pintype "input"))
    )
    (net (code "41") (name "Net-(U1-PC0(ADC0{slash}PCINT8))") (class "Default")
      (node (ref "R2") (pin "2") (pinfunction "2_2") (pintype "input"))
      (node (ref "U1") (pin "23") (pinfunction "PC0(ADC0/PCINT8)_23") (pintype "input"))
    )
    (net (code "42") (name "Net-(U1-PC1(ADC1{slash}PCINT9))") (class "Default")
      (node (ref "R1") (pin "2") (pinfunction "2_2") (pintype "input"))
      (node (ref "U1") (pin "24") (pinfunction "PC1(ADC1/PCINT9)_24") (pintype "input"))
    )
    (net (code "43") (name "Net-(U1-PC6(RESET#{slash}PCINT14))") (class "Default")
      (node (ref "C5") (pin "2") (pinfunction "2_2") (pintype "input"))
      (node (ref "P2") (pin "5") (pinfunction "5_5") (pintype "input"))
      (node (ref "R19") (pin "1") (pinfunction "1_1") (pintype "input"))
      (node (ref "SW1") (pin "2") (pinfunction "2_2") (pintype "input"))
      (node (ref "U1") (pin "29") (pinfunction "PC6(RESET#/PCINT14)_29") (pintype "input"))
    )
    (net (code "44") (name "Net-(U1-PD0(RXD{slash}PCINT16))") (class "Default")
      (node (ref "FTDI") (pin "4") (pinfunction "4_4") (pintype "input"))
      (node (ref "U1") (pin "30") (pinfunction "PD0(RXD/PCINT16)_30") (pintype "input"))
    )
    (net (code "45") (name "Net-(U1-PD1(TXD{slash}PCINT17))") (class "Default")
      (node (ref "FTDI") (pin "5") (pinfunction "5_5") (pintype "input"))
      (node (ref "U1") (pin "31") (pinfunction "PD1(TXD/PCINT17)_31") (pintype "input"))
    )
    (net (code "46") (name "SCL") (class "Default")
      (node (ref "RJ3") (pin "6") (pinfunction "6_6") (pintype "input"))
      (node (ref "RJ4") (pin "6") (pinfunction "6_6") (pintype "input"))
      (node (ref "U1") (pin "28") (pinfunction "PC5(ADC5/SCL/PCINT13)_28") (pintype "input"))
    )
    (net (code "47") (name "SDA") (class "Default")
      (node (ref "RJ3") (pin "3") (pinfunction "3_3") (pintype "input"))
      (node (ref "RJ4") (pin "3") (pinfunction "3_3") (pintype "input"))
      (node (ref "U1") (pin "27") (pinfunction "PC4(ADC4/SDA/PCINT12)_27") (pintype "input"))
    )
    (net (code "48") (name "VCC") (class "Default")
      (node (ref "C3") (pin "1") (pinfunction "1_1") (pintype "input"))
      (node (ref "C4") (pin "2") (pinfunction "2_2") (pintype "input"))
      (node (ref "FTDI") (pin "3") (pinfunction "3_3") (pintype "input"))
      (node (ref "P2") (pin "2") (pinfunction "2_2") (pintype "input"))
      (node (ref "Q1") (pin "2") (pinfunction "S_2") (pintype "input"))
      (node (ref "Q2") (pin "2") (pinfunction "S_2") (pintype "input"))
      (node (ref "Q3") (pin "2") (pinfunction "S_2") (pintype "input"))
      (node (ref "Q4") (pin "2") (pinfunction "S_2") (pintype "input"))
      (node (ref "Q5") (pin "2") (pinfunction "S_2") (pintype "input"))
      (node (ref "Q6") (pin "2") (pinfunction "S_2") (pintype "input"))
      (node (ref "Q7") (pin "2") (pinfunction "S_2") (pintype "input"))
      (node (ref "Q8") (pin "2") (pinfunction "S_2") (pintype "input"))
      (node (ref "R11") (pin "2") (pinfunction "2_2") (pintype "input"))
      (node (ref "R12") (pin "2") (pinfunction "2_2") (pintype "input"))
      (node (ref "R19") (pin "2") (pinfunction "2_2") (pintype "input"))
      (node (ref "R20") (pin "2") (pinfunction "2_2") (pintype "input"))
      (node (ref "R21") (pin "2") (pinfunction "2_2") (pintype "input"))
      (node (ref "R22") (pin "2") (pinfunction "2_2") (pintype "input"))
      (node (ref "R23") (pin "2") (pinfunction "2_2") (pintype "input"))
      (node (ref "R24") (pin "2") (pinfunction "2_2") (pintype "input"))
      (node (ref "R25") (pin "2") (pinfunction "2_2") (pintype "input"))
      (node (ref "R26") (pin "2") (pinfunction "2_2") (pintype "input"))
      (node (ref "RJ3") (pin "1") (pinfunction "1_1") (pintype "input"))
      (node (ref "RJ4") (pin "1") (pinfunction "1_1") (pintype "input"))
      (node (ref "U1") (pin "4") (pinfunction "VCC_4") (pintype "input"))
      (node (ref "U1") (pin "6") (pinfunction "VCC_6") (pintype "input"))
    )
    (net (code "49") (name "unconnected-(RJ3-Pad2)") (class "Default")
      (node (ref "RJ3") (pin "2") (pinfunction "2_2") (pintype "input+no_connect"))
    )
    (net (code "50") (name "unconnected-(RJ3-Pad7)") (class "Default")
      (node (ref "RJ3") (pin "7") (pinfunction "7_7") (pintype "input+no_connect"))
    )
    (net (code "51") (name "unconnected-(RJ4-Pad2)") (class "Default")
      (node (ref "RJ4") (pin "2") (pinfunction "2_2") (pintype "input+no_connect"))
    )
    (net (code "52") (name "unconnected-(RJ4-Pad7)") (class "Default")
      (node (ref "RJ4") (pin "7") (pinfunction "7_7") (pintype "input+no_connect"))
    )
    (net (code "53") (name "unconnected-(U1-(PCINT19{slash}OC2B{slash}INT1)PD3-Pad1)") (class "Default")
      (node (ref "U1") (pin "1") (pinfunction "(PCINT19/OC2B/INT1)PD3_1") (pintype "input"))
    )
    (net (code "54") (name "unconnected-(U1-(PCINT20{slash}XCK{slash}T0)PD4-Pad2)") (class "Default")
      (node (ref "U1") (pin "2") (pinfunction "(PCINT20/XCK/T0)PD4_2") (pintype "input"))
    )
    (net (code "55") (name "unconnected-(U1-ADC6-Pad19)") (class "Default")
      (node (ref "U1") (pin "19") (pinfunction "ADC6_19") (pintype "input"))
    )
    (net (code "56") (name "unconnected-(U1-ADC7-Pad22)") (class "Default")
      (node (ref "U1") (pin "22") (pinfunction "ADC7_22") (pintype "input"))
    )
    (net (code "57") (name "unconnected-(U1-AREF-Pad20)") (class "Default")
      (node (ref "U1") (pin "20") (pinfunction "AREF_20") (pintype "input"))
    )
    (net (code "58") (name "unconnected-(U1-AVCC-Pad18)") (class "Default")
      (node (ref "U1") (pin "18") (pinfunction "AVCC_18") (pintype "input"))
    )
    (net (code "59") (name "unconnected-(U1-PC2(ADC2{slash}PCINT10)-Pad25)") (class "Default")
      (node (ref "U1") (pin "25") (pinfunction "PC2(ADC2/PCINT10)_25") (pintype "input"))
    )
    (net (code "60") (name "unconnected-(U1-PC3(ADC3{slash}PCINT11)-Pad26)") (class "Default")
      (node (ref "U1") (pin "26") (pinfunction "PC3(ADC3/PCINT11)_26") (pintype "input"))
    )
    (net (code "61") (name "unconnected-(U1-PD2(INT0{slash}PCINT18)-Pad32)") (class "Default")
      (node (ref "U1") (pin "32") (pinfunction "PD2(INT0/PCINT18)_32") (pintype "input"))
    )
  )
)
